# power.net
KiCad netlist of a schematic drawn in Altium Designer
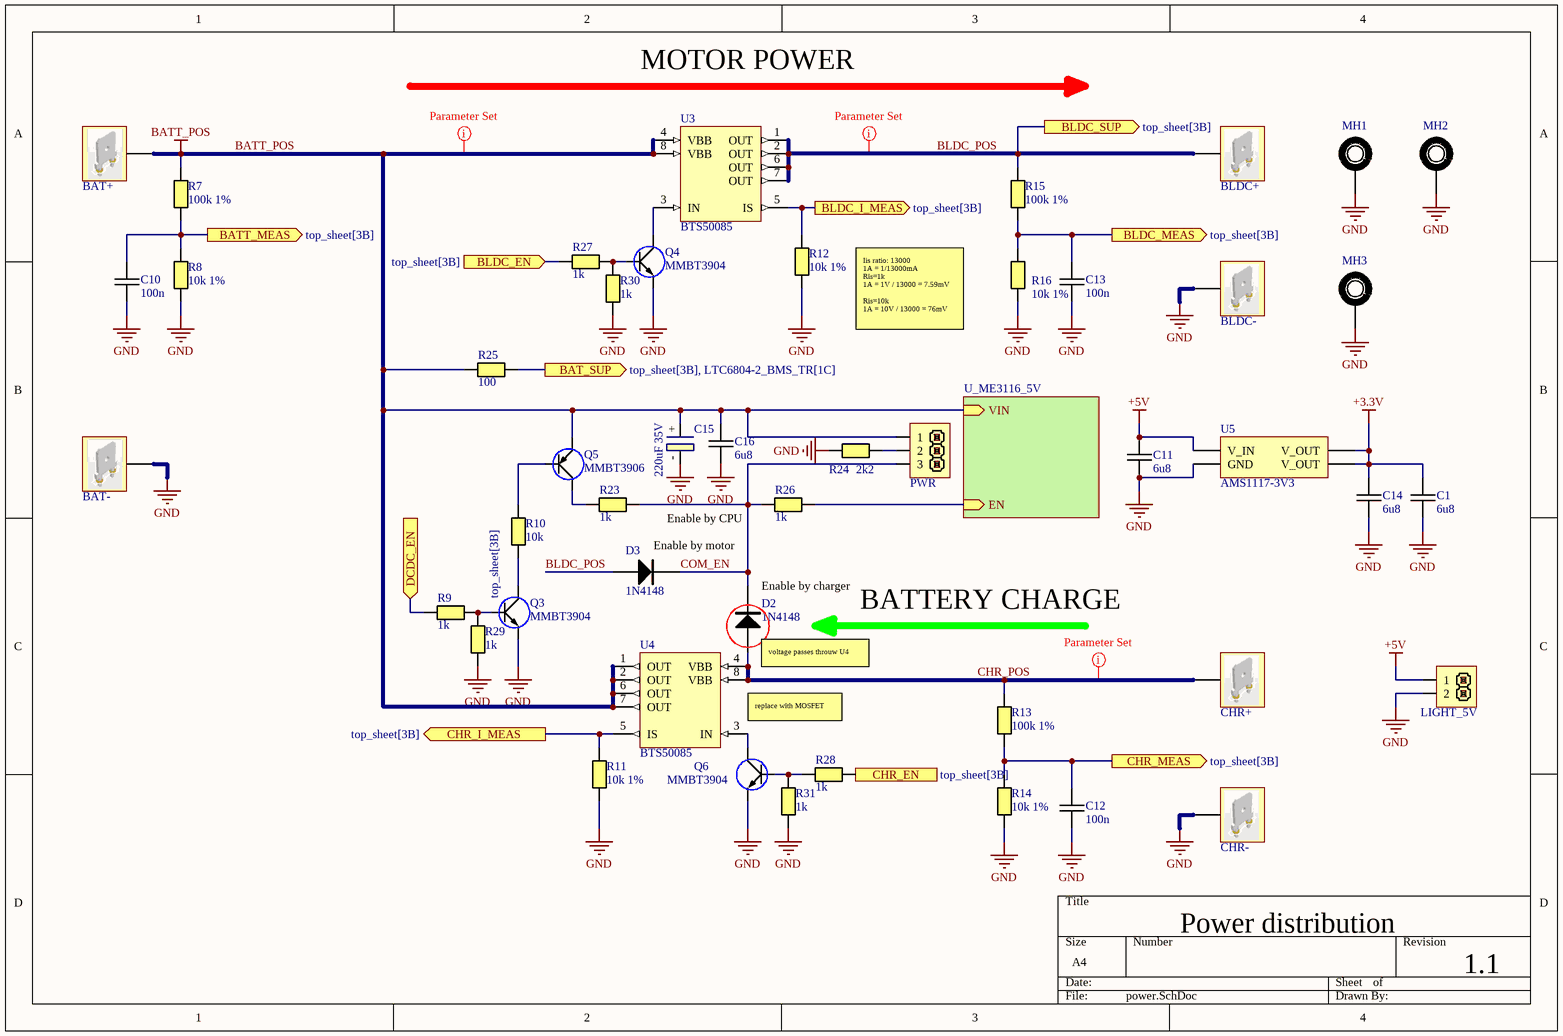
[diagram p0: power.SchDoc]

(export (version "E")
  (design (tool "Eeschema 10.0.6"))
  (components
    (comp (ref "BAT+")
      (value "Crimp 6.3 single PCB")
      (footprint "Crimp 6.3mm single PCB")
      (description "Straight Mount Angle PCB Tab Terminal")
      (libsource (lib "") (part "Crimp 6.3 single PCB_1"))
    )
    (comp (ref "BAT-")
      (value "Crimp 6.3 single PCB")
      (footprint "Crimp 6.3mm single PCB")
      (description "Straight Mount Angle PCB Tab Terminal")
      (libsource (lib "") (part "Crimp 6.3 single PCB_1"))
    )
    (comp (ref "BLDC+")
      (value "Crimp 6.3 single PCB")
      (footprint "Crimp 6.3mm single PCB")
      (description "Straight Mount Angle PCB Tab Terminal")
      (libsource (lib "Connectors") (part "Crimp 6.3 single PCB"))
    )
    (comp (ref "BLDC-")
      (value "Crimp 6.3 single PCB")
      (footprint "Crimp 6.3mm single PCB")
      (description "Straight Mount Angle PCB Tab Terminal")
      (libsource (lib "Connectors") (part "Crimp 6.3 single PCB"))
    )
    (comp (ref "C1")
      (value "6u8")
      (footprint "CAPC0805(2012)75_N")
      (description "Ceramic capacitor Medium density")
      (libsource (lib "Discrete") (part "Capacitor M"))
    )
    (comp (ref "C10")
      (value "100n")
      (footprint "CAPC0805(2012)75_N")
      (description "Ceramic capacitor Medium density")
      (libsource (lib "Discrete") (part "Capacitor M"))
    )
    (comp (ref "C11")
      (value "6u8")
      (footprint "CAPC0805(2012)75_N")
      (description "Ceramic capacitor Medium density")
      (libsource (lib "Discrete") (part "Capacitor M"))
    )
    (comp (ref "C12")
      (value "100n")
      (footprint "CAPC0805(2012)75_N")
      (description "Ceramic capacitor Medium density")
      (libsource (lib "Discrete") (part "Capacitor M"))
    )
    (comp (ref "C13")
      (value "100n")
      (footprint "CAPC0805(2012)75_N")
      (description "Ceramic capacitor Medium density")
      (libsource (lib "Discrete") (part "Capacitor M"))
    )
    (comp (ref "C14")
      (value "6u8")
      (footprint "CAPC0805(2012)75_N")
      (description "Ceramic capacitor Medium density")
      (libsource (lib "Discrete") (part "Capacitor M"))
    )
    (comp (ref "C15")
      (value "220uF 35V")
      (footprint "10x10.5 Capacitor")
      (description "Capacitor Electrolitic")
      (libsource (lib "Discrete") (part "Capacitor Electrolitic"))
    )
    (comp (ref "C16")
      (value "6u8")
      (footprint "CAPC0805(2012)75_N")
      (description "Ceramic capacitor Medium density")
      (libsource (lib "Discrete") (part "Capacitor M"))
    )
    (comp (ref "CHR+")
      (value "Crimp 6.3 single PCB")
      (footprint "Crimp 6.3mm single PCB")
      (description "Straight Mount Angle PCB Tab Terminal")
      (libsource (lib "Connectors") (part "Crimp 6.3 single PCB"))
    )
    (comp (ref "CHR-")
      (value "Crimp 6.3 single PCB")
      (footprint "Crimp 6.3mm single PCB")
      (description "Straight Mount Angle PCB Tab Terminal")
      (libsource (lib "Connectors") (part "Crimp 6.3 single PCB"))
    )
    (comp (ref "CN1")
      (value "PIN HEADER 1x2")
      (footprint "XH2.54 2P")
      (description "LIGHT_5V")
      (fields (field (name "PARAMETER 1") "LIGHT_5V"))
      (libsource (lib "Connectors") (part "PIN HEADER 2.54 1x2"))
    )
    (comp (ref "D2")
      (value "1N4148")
      (footprint "SOD80")
      (description "Small Signal Fast Switching Diodes")
      (libsource (lib "Diodes") (part "1N4148"))
    )
    (comp (ref "D3")
      (value "1N4148")
      (footprint "SOD80")
      (description "Small Signal Fast Switching Diodes")
      (libsource (lib "Diodes") (part "1N4148"))
    )
    (comp (ref "MH1")
      (value "Mounting Hole")
      (footprint "MH_M3")
      (libsource (lib "Connectors") (part "Mounting Hole"))
    )
    (comp (ref "MH2")
      (value "Mounting Hole")
      (footprint "MH_M3")
      (libsource (lib "Connectors") (part "Mounting Hole"))
    )
    (comp (ref "MH3")
      (value "Mounting Hole")
      (footprint "MH_M3")
      (libsource (lib "Connectors") (part "Mounting Hole"))
    )
    (comp (ref "PWR")
      (value "PIN HEADER 1x3")
      (footprint "XH2.54 3P")
      (libsource (lib "Connectors") (part "PIN HEADER 2.54 1x3"))
    )
    (comp (ref "Q3")
      (value "MMBT3904")
      (footprint "SOT23")
      (description "NPN General Purpose Transistor")
      (libsource (lib "Transistors") (part "2N3904"))
    )
    (comp (ref "Q4")
      (value "MMBT3904")
      (footprint "SOT23")
      (description "NPN General Purpose Transistor")
      (libsource (lib "Transistors") (part "2N3904"))
    )
    (comp (ref "Q5")
      (value "MMBT3906")
      (footprint "SOT23")
      (description "PNP General Purpose Transistor")
      (libsource (lib "Transistors") (part "2N3906"))
    )
    (comp (ref "Q6")
      (value "MMBT3904")
      (footprint "SOT23")
      (description "NPN General Purpose Transistor")
      (libsource (lib "Transistors") (part "2N3904"))
    )
    (comp (ref "R7")
      (value "100k 1%")
      (footprint "RESC0603(1608)_N")
      (description "Resistor Medium Density")
      (libsource (lib "") (part "Resistor M_1"))
    )
    (comp (ref "R8")
      (value "10k 1%")
      (footprint "RESC0603(1608)_N")
      (description "Resistor Medium Density")
      (libsource (lib "") (part "Resistor M_1"))
    )
    (comp (ref "R9")
      (value "1k")
      (footprint "RESC0603(1608)_N")
      (description "Resistor Medium Density")
      (libsource (lib "") (part "Resistor M_3"))
    )
    (comp (ref "R10")
      (value "10k")
      (footprint "RESC0603(1608)_N")
      (description "Resistor Medium Density")
      (libsource (lib "") (part "Resistor M_2"))
    )
    (comp (ref "R11")
      (value "10k 1%")
      (footprint "RESC0603(1608)_N")
      (description "Resistor Medium Density")
      (libsource (lib "") (part "Resistor M_1"))
    )
    (comp (ref "R12")
      (value "10k 1%")
      (footprint "RESC0603(1608)_N")
      (description "Resistor Medium Density")
      (libsource (lib "") (part "Resistor M_1"))
    )
    (comp (ref "R13")
      (value "100k 1%")
      (footprint "RESC0603(1608)_N")
      (description "Resistor Medium Density")
      (libsource (lib "") (part "Resistor M_1"))
    )
    (comp (ref "R14")
      (value "10k 1%")
      (footprint "RESC0603(1608)_N")
      (description "Resistor Medium Density")
      (libsource (lib "") (part "Resistor M_1"))
    )
    (comp (ref "R15")
      (value "100k 1%")
      (footprint "RESC0603(1608)_N")
      (description "Resistor Medium Density")
      (libsource (lib "") (part "Resistor M_1"))
    )
    (comp (ref "R16")
      (value "10k 1%")
      (footprint "RESC0603(1608)_N")
      (description "Resistor Medium Density")
      (libsource (lib "") (part "Resistor M_1"))
    )
    (comp (ref "R23")
      (value "1k")
      (footprint "RESC0603(1608)_N")
      (description "Resistor Medium Density")
      (libsource (lib "Discrete") (part "Resistor M"))
    )
    (comp (ref "R24")
      (value "2k2")
      (footprint "RESC0603(1608)_N")
      (description "Resistor Medium Density")
      (libsource (lib "Discrete") (part "Resistor M"))
    )
    (comp (ref "R25")
      (value "100")
      (footprint "RESC0603(1608)_N")
      (description "Resistor Medium Density")
      (libsource (lib "Discrete") (part "Resistor M"))
    )
    (comp (ref "R26")
      (value "1k")
      (footprint "RESC0603(1608)_N")
      (description "Resistor Medium Density")
      (libsource (lib "Discrete") (part "Resistor M"))
    )
    (comp (ref "R27")
      (value "1k")
      (footprint "RESC0603(1608)_N")
      (description "Resistor Medium Density")
      (libsource (lib "") (part "Resistor M_3"))
    )
    (comp (ref "R28")
      (value "1k")
      (footprint "RESC0603(1608)_N")
      (description "Resistor Medium Density")
      (libsource (lib "") (part "Resistor M_2"))
    )
    (comp (ref "R29")
      (value "1k")
      (footprint "RESC0603(1608)_N")
      (description "Resistor Medium Density")
      (libsource (lib "") (part "Resistor M_1"))
    )
    (comp (ref "R30")
      (value "1k")
      (footprint "RESC0603(1608)_N")
      (description "Resistor Medium Density")
      (libsource (lib "") (part "Resistor M_1"))
    )
    (comp (ref "R31")
      (value "1k")
      (footprint "RESC0603(1608)_N")
      (description "Resistor Medium Density")
      (libsource (lib "") (part "Resistor M_1"))
    )
    (comp (ref "U3")
      (value "BTS50085")
      (footprint "PG-TO220-7-4")
      (description "Smart Highside High Current Power Switch")
      (libsource (lib "Switches") (part "BTS50085-1TMA"))
    )
    (comp (ref "U4")
      (value "BTS50085")
      (footprint "PG-TO220-7-4")
      (description "Smart Highside High Current Power Switch")
      (libsource (lib "") (part "BTS50085-1TMA_1"))
    )
    (comp (ref "U5")
      (value "AMS1117-3V3")
      (footprint "SOT229P700X180-4N")
      (description "800mA LDO  15V max")
      (libsource (lib "VoltageRegulators") (part "AMS1117"))
    )
  )
  (nets
    (net (code "1") (name "+3.3V") (class "Default")
      (node (ref "C1") (pin "1") (pinfunction "1_1") (pintype "passive"))
      (node (ref "C14") (pin "1") (pinfunction "1_1") (pintype "passive"))
      (node (ref "U5") (pin "2") (pinfunction "V_OUT_2") (pintype "passive"))
      (node (ref "U5") (pin "4") (pinfunction "V_OUT_4") (pintype "passive"))
    )
    (net (code "2") (name "+5V") (class "Default")
      (node (ref "C11") (pin "1") (pinfunction "1_1") (pintype "passive"))
      (node (ref "CN1") (pin "1") (pinfunction "1_1") (pintype "passive"))
      (node (ref "U5") (pin "3") (pinfunction "V_IN_3") (pintype "passive"))
    )
    (net (code "3") (name "/BATT_MEAS") (class "Default")
      (node (ref "C10") (pin "1") (pinfunction "1_1") (pintype "passive"))
      (node (ref "R7") (pin "1") (pinfunction "1_1") (pintype "passive"))
      (node (ref "R8") (pin "2") (pinfunction "2_2") (pintype "passive"))
    )
    (net (code "4") (name "/BAT_SUP") (class "Default")
      (node (ref "R25") (pin "1") (pinfunction "1_1") (pintype "passive"))
    )
    (net (code "5") (name "/BLDC_EN") (class "Default")
      (node (ref "R27") (pin "1") (pinfunction "1_1") (pintype "passive"))
    )
    (net (code "6") (name "/BLDC_I_MEAS") (class "Default")
      (node (ref "R12") (pin "2") (pinfunction "2_2") (pintype "passive"))
      (node (ref "U3") (pin "5") (pinfunction "IS_5") (pintype "output"))
    )
    (net (code "7") (name "/BLDC_MEAS") (class "Default")
      (node (ref "C13") (pin "1") (pinfunction "1_1") (pintype "passive"))
      (node (ref "R15") (pin "1") (pinfunction "1_1") (pintype "passive"))
      (node (ref "R16") (pin "2") (pinfunction "2_2") (pintype "passive"))
    )
    (net (code "8") (name "/BLDC_POS") (class "Default")
      (node (ref "BLDC+") (pin "1") (pintype "passive"))
      (node (ref "D3") (pin "1") (pinfunction "A_1") (pintype "passive"))
      (node (ref "R15") (pin "2") (pinfunction "2_2") (pintype "passive"))
      (node (ref "U3") (pin "1") (pinfunction "OUT_1") (pintype "output"))
      (node (ref "U3") (pin "2") (pinfunction "OUT_2") (pintype "output"))
      (node (ref "U3") (pin "6") (pinfunction "OUT_6") (pintype "output"))
      (node (ref "U3") (pin "7") (pinfunction "OUT_7") (pintype "output"))
    )
    (net (code "9") (name "/CHR_EN") (class "Default")
      (node (ref "R28") (pin "1") (pinfunction "1_1") (pintype "passive"))
    )
    (net (code "10") (name "/CHR_I_MEAS") (class "Default")
      (node (ref "R11") (pin "2") (pinfunction "2_2") (pintype "passive"))
      (node (ref "U4") (pin "5") (pinfunction "IS_5") (pintype "output"))
    )
    (net (code "11") (name "/CHR_MEAS") (class "Default")
      (node (ref "C12") (pin "1") (pinfunction "1_1") (pintype "passive"))
      (node (ref "R13") (pin "1") (pinfunction "1_1") (pintype "passive"))
      (node (ref "R14") (pin "2") (pinfunction "2_2") (pintype "passive"))
    )
    (net (code "12") (name "/CHR_POS") (class "Default")
      (node (ref "CHR+") (pin "1") (pintype "passive"))
      (node (ref "D2") (pin "1") (pinfunction "A_1") (pintype "passive"))
      (node (ref "R13") (pin "2") (pinfunction "2_2") (pintype "passive"))
      (node (ref "U4") (pin "4") (pinfunction "VBB_4") (pintype "input"))
      (node (ref "U4") (pin "8") (pinfunction "VBB_8") (pintype "input"))
    )
    (net (code "13") (name "/COM_EN") (class "Default")
      (node (ref "D2") (pin "2") (pinfunction "K_2") (pintype "passive"))
      (node (ref "D3") (pin "2") (pinfunction "K_2") (pintype "passive"))
      (node (ref "PWR") (pin "3") (pinfunction "3_3") (pintype "passive"))
      (node (ref "R23") (pin "1") (pinfunction "1_1") (pintype "passive"))
      (node (ref "R26") (pin "2") (pinfunction "2_2") (pintype "passive"))
    )
    (net (code "14") (name "/DCDC_EN") (class "Default")
      (node (ref "R9") (pin "1") (pinfunction "1_1") (pintype "passive"))
    )
    (net (code "15") (name "/EN") (class "Default")
      (node (ref "R26") (pin "1") (pinfunction "1_1") (pintype "passive"))
    )
    (net (code "16") (name "BATT_POS") (class "Default")
      (node (ref "BAT+") (pin "1") (pintype "passive"))
      (node (ref "C15") (pin "+") (pinfunction "+_+") (pintype "passive"))
      (node (ref "C16") (pin "2") (pinfunction "2_2") (pintype "passive"))
      (node (ref "PWR") (pin "1") (pinfunction "1_1") (pintype "passive"))
      (node (ref "Q5") (pin "2") (pinfunction "E_2") (pintype "passive"))
      (node (ref "R25") (pin "2") (pinfunction "2_2") (pintype "passive"))
      (node (ref "R7") (pin "2") (pinfunction "2_2") (pintype "passive"))
      (node (ref "U3") (pin "4") (pinfunction "VBB_4") (pintype "input"))
      (node (ref "U3") (pin "8") (pinfunction "VBB_8") (pintype "input"))
      (node (ref "U4") (pin "1") (pinfunction "OUT_1") (pintype "output"))
      (node (ref "U4") (pin "2") (pinfunction "OUT_2") (pintype "output"))
      (node (ref "U4") (pin "6") (pinfunction "OUT_6") (pintype "output"))
      (node (ref "U4") (pin "7") (pinfunction "OUT_7") (pintype "output"))
    )
    (net (code "17") (name "GND") (class "Default")
      (node (ref "BAT-") (pin "1") (pintype "passive"))
      (node (ref "BLDC-") (pin "1") (pintype "passive"))
      (node (ref "C1") (pin "2") (pinfunction "2_2") (pintype "passive"))
      (node (ref "C10") (pin "2") (pinfunction "2_2") (pintype "passive"))
      (node (ref "C11") (pin "2") (pinfunction "2_2") (pintype "passive"))
      (node (ref "C12") (pin "2") (pinfunction "2_2") (pintype "passive"))
      (node (ref "C13") (pin "2") (pinfunction "2_2") (pintype "passive"))
      (node (ref "C14") (pin "2") (pinfunction "2_2") (pintype "passive"))
      (node (ref "C15") (pin "-") (pinfunction "-_-") (pintype "passive"))
      (node (ref "C16") (pin "1") (pinfunction "1_1") (pintype "passive"))
      (node (ref "CHR-") (pin "1") (pintype "passive"))
      (node (ref "CN1") (pin "2") (pinfunction "2_2") (pintype "passive"))
      (node (ref "MH1") (pin "1") (pintype "passive"))
      (node (ref "MH2") (pin "1") (pintype "passive"))
      (node (ref "MH3") (pin "1") (pintype "passive"))
      (node (ref "Q3") (pin "2") (pinfunction "E_2") (pintype "passive"))
      (node (ref "Q4") (pin "2") (pinfunction "E_2") (pintype "passive"))
      (node (ref "Q6") (pin "2") (pinfunction "E_2") (pintype "passive"))
      (node (ref "R11") (pin "1") (pinfunction "1_1") (pintype "passive"))
      (node (ref "R12") (pin "1") (pinfunction "1_1") (pintype "passive"))
      (node (ref "R14") (pin "1") (pinfunction "1_1") (pintype "passive"))
      (node (ref "R16") (pin "1") (pinfunction "1_1") (pintype "passive"))
      (node (ref "R24") (pin "2") (pinfunction "2_2") (pintype "passive"))
      (node (ref "R29") (pin "1") (pinfunction "1_1") (pintype "passive"))
      (node (ref "R30") (pin "1") (pinfunction "1_1") (pintype "passive"))
      (node (ref "R31") (pin "1") (pinfunction "1_1") (pintype "passive"))
      (node (ref "R8") (pin "1") (pinfunction "1_1") (pintype "passive"))
      (node (ref "U5") (pin "1") (pinfunction "GND_1") (pintype "passive"))
    )
    (net (code "18") (name "Net-(PWR-Pad2)") (class "Default")
      (node (ref "PWR") (pin "2") (pinfunction "2_2") (pintype "passive"))
      (node (ref "R24") (pin "1") (pinfunction "1_1") (pintype "passive"))
    )
    (net (code "19") (name "Net-(Q3-B)") (class "Default")
      (node (ref "Q3") (pin "1") (pinfunction "B_1") (pintype "passive"))
      (node (ref "R29") (pin "2") (pinfunction "2_2") (pintype "passive"))
      (node (ref "R9") (pin "2") (pinfunction "2_2") (pintype "passive"))
    )
    (net (code "20") (name "Net-(Q3-C)") (class "Default")
      (node (ref "Q3") (pin "3") (pinfunction "C_3") (pintype "passive"))
      (node (ref "R10") (pin "2") (pinfunction "2_2") (pintype "passive"))
    )
    (net (code "21") (name "Net-(Q4-B)") (class "Default")
      (node (ref "Q4") (pin "1") (pinfunction "B_1") (pintype "passive"))
      (node (ref "R27") (pin "2") (pinfunction "2_2") (pintype "passive"))
      (node (ref "R30") (pin "2") (pinfunction "2_2") (pintype "passive"))
    )
    (net (code "22") (name "Net-(Q4-C)") (class "Default")
      (node (ref "Q4") (pin "3") (pinfunction "C_3") (pintype "passive"))
      (node (ref "U3") (pin "3") (pinfunction "IN_3") (pintype "input"))
    )
    (net (code "23") (name "Net-(Q5-B)") (class "Default")
      (node (ref "Q5") (pin "1") (pinfunction "B_1") (pintype "passive"))
      (node (ref "R10") (pin "1") (pinfunction "1_1") (pintype "passive"))
    )
    (net (code "24") (name "Net-(Q5-C)") (class "Default")
      (node (ref "Q5") (pin "3") (pinfunction "C_3") (pintype "passive"))
      (node (ref "R23") (pin "2") (pinfunction "2_2") (pintype "passive"))
    )
    (net (code "25") (name "Net-(Q6-B)") (class "Default")
      (node (ref "Q6") (pin "1") (pinfunction "B_1") (pintype "passive"))
      (node (ref "R28") (pin "2") (pinfunction "2_2") (pintype "passive"))
      (node (ref "R31") (pin "2") (pinfunction "2_2") (pintype "passive"))
    )
    (net (code "26") (name "Net-(Q6-C)") (class "Default")
      (node (ref "Q6") (pin "3") (pinfunction "C_3") (pintype "passive"))
      (node (ref "U4") (pin "3") (pinfunction "IN_3") (pintype "input"))
    )
  )
)
